# power_supply.net
KiCad netlist of a schematic drawn in Altium Designer
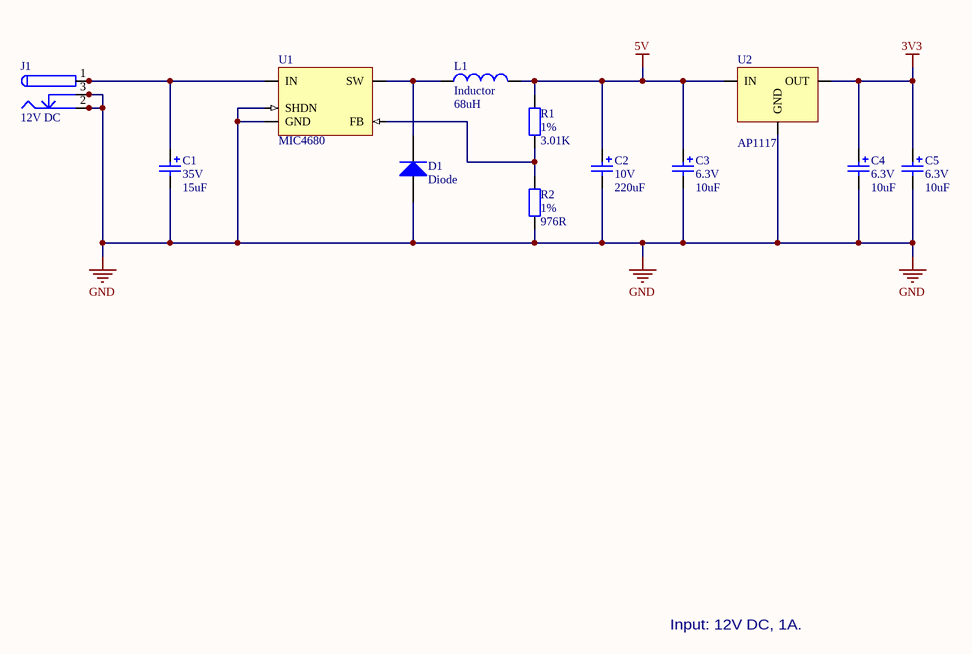
[diagram p0: power_supply.SchDoc]

(export (version "E")
  (design (tool "Eeschema 10.0.6"))
  (components
    (comp (ref "C1")
      (value "35V")
      (footprint "EIA-7343")
      (description "Polarized Capacitor (Axial)")
      (fields (field (name "ALTIUM_VALUE") "15uF") (field (name "PUBLISHER") "Altium Limited"))
      (libsource (lib "Miscellaneous Devices") (part "Cap Pol2"))
    )
    (comp (ref "C2")
      (value "10V")
      (footprint "EIA-7343")
      (description "Polarized Capacitor (Axial)")
      (fields (field (name "ALTIUM_VALUE") "220uF") (field (name "PUBLISHER") "Altium Limited"))
      (libsource (lib "Miscellaneous Devices") (part "Cap Pol2"))
    )
    (comp (ref "C3")
      (value "6.3V")
      (footprint "EIA-3216")
      (description "Polarized Capacitor (Axial)")
      (fields (field (name "ALTIUM_VALUE") "10uF") (field (name "PUBLISHER") "Altium Limited"))
      (libsource (lib "Miscellaneous Devices") (part "Cap Pol2"))
    )
    (comp (ref "C4")
      (value "6.3V")
      (footprint "EIA-3216")
      (description "Polarized Capacitor (Axial)")
      (fields (field (name "ALTIUM_VALUE") "10uF") (field (name "PUBLISHER") "Altium Limited"))
      (libsource (lib "Miscellaneous Devices") (part "Cap Pol2"))
    )
    (comp (ref "C5")
      (value "6.3V")
      (footprint "EIA-3216")
      (description "Polarized Capacitor (Axial)")
      (fields (field (name "ALTIUM_VALUE") "10uF") (field (name "PUBLISHER") "Altium Limited"))
      (libsource (lib "Miscellaneous Devices") (part "Cap Pol2"))
    )
    (comp (ref "D1")
      (value "Diode")
      (footprint "Diode (SMA)")
      (description "Default Diode")
      (fields (field (name "PUBLISHER") "Altium Limited"))
      (libsource (lib "Miscellaneous Devices") (part "Diode"))
    )
    (comp (ref "J1")
      (value "12V DC")
      (footprint "DC Jack")
      (description "Low Voltage Power Supply Connector")
      (fields (field (name "PUBLISHER") "Altium Limited"))
      (libsource (lib "Miscellaneous Connectors") (part "PWR2.5"))
    )
    (comp (ref "L1")
      (value "Inductor")
      (footprint "Inductor EPCOS")
      (fields (field (name "ALTIUM_VALUE") "68uH") (field (name "PUBLISHER") "Altium Limited"))
      (libsource (lib "Miscellaneous Devices") (part "Inductor"))
    )
    (comp (ref "R1")
      (value "1%")
      (footprint "0603")
      (description "Resistor")
      (fields (field (name "ALTIUM_VALUE") "3.01K") (field (name "PUBLISHER") "Altium Limited"))
      (libsource (lib "Miscellaneous Devices") (part "Res2"))
    )
    (comp (ref "R2")
      (value "1%")
      (footprint "0603")
      (description "Resistor")
      (fields (field (name "ALTIUM_VALUE") "976R") (field (name "PUBLISHER") "Altium Limited"))
      (libsource (lib "Miscellaneous Devices") (part "Res2"))
    )
    (comp (ref "U1")
      (value "MIC4680")
      (footprint "SO-8")
      (description "1A 200kHz Buck Regulator")
      (libsource (lib "AJ") (part "MIC4680"))
    )
    (comp (ref "U2")
      (value "AP1117")
      (footprint "TO252 HS")
      (description "Low Dropout Regulator")
      (libsource (lib "AJ") (part "AP1117"))
    )
  )
  (nets
    (net (code "1") (name "3V3") (class "Default")
      (node (ref "C4") (pin "1") (pinfunction "1_1") (pintype "passive"))
      (node (ref "C5") (pin "1") (pinfunction "1_1") (pintype "passive"))
      (node (ref "U2") (pin "2") (pinfunction "OUT_2") (pintype "passive"))
    )
    (net (code "2") (name "5V") (class "Default")
      (node (ref "C2") (pin "1") (pinfunction "1_1") (pintype "passive"))
      (node (ref "C3") (pin "1") (pinfunction "1_1") (pintype "passive"))
      (node (ref "L1") (pin "2") (pinfunction "2_2") (pintype "passive"))
      (node (ref "R1") (pin "2") (pinfunction "2_2") (pintype "passive"))
      (node (ref "U2") (pin "3") (pinfunction "IN_3") (pintype "passive"))
    )
    (net (code "3") (name "GND") (class "Default")
      (node (ref "C1") (pin "2") (pinfunction "2_2") (pintype "passive"))
      (node (ref "C2") (pin "2") (pinfunction "2_2") (pintype "passive"))
      (node (ref "C3") (pin "2") (pinfunction "2_2") (pintype "passive"))
      (node (ref "C4") (pin "2") (pinfunction "2_2") (pintype "passive"))
      (node (ref "C5") (pin "2") (pinfunction "2_2") (pintype "passive"))
      (node (ref "D1") (pin "1") (pinfunction "A_1") (pintype "passive"))
      (node (ref "J1") (pin "2") (pinfunction "2_2") (pintype "power_in"))
      (node (ref "J1") (pin "2A") (pinfunction "2A_2A") (pintype "power_in"))
      (node (ref "J1") (pin "2B") (pinfunction "2B_2B") (pintype "power_in"))
      (node (ref "J1") (pin "3") (pinfunction "3_3") (pintype "power_in"))
      (node (ref "J1") (pin "3A") (pinfunction "3A_3A") (pintype "power_in"))
      (node (ref "J1") (pin "3B") (pinfunction "3B_3B") (pintype "power_in"))
      (node (ref "R2") (pin "1") (pinfunction "1_1") (pintype "passive"))
      (node (ref "U1") (pin "1") (pinfunction "SHDN_1") (pintype "input"))
      (node (ref "U1") (pin "5") (pinfunction "GND_5") (pintype "power_in"))
      (node (ref "U1") (pin "6") (pinfunction "GND_6") (pintype "power_in"))
      (node (ref "U1") (pin "7") (pinfunction "GND_7") (pintype "power_in"))
      (node (ref "U1") (pin "8") (pinfunction "GND_8") (pintype "power_in"))
      (node (ref "U2") (pin "1") (pinfunction "GND_1") (pintype "power_in"))
    )
    (net (code "4") (name "Net-(D1-K)") (class "Default")
      (node (ref "D1") (pin "2") (pinfunction "K_2") (pintype "passive"))
      (node (ref "L1") (pin "1") (pinfunction "1_1") (pintype "passive"))
      (node (ref "U1") (pin "3") (pinfunction "SW_3") (pintype "passive"))
    )
    (net (code "5") (name "Net-(U1-FB)") (class "Default")
      (node (ref "R1") (pin "1") (pinfunction "1_1") (pintype "passive"))
      (node (ref "R2") (pin "2") (pinfunction "2_2") (pintype "passive"))
      (node (ref "U1") (pin "4") (pinfunction "FB_4") (pintype "input"))
    )
    (net (code "6") (name "Net-(U1-IN)") (class "Default")
      (node (ref "C1") (pin "1") (pinfunction "1_1") (pintype "passive"))
      (node (ref "J1") (pin "1") (pinfunction "1_1") (pintype "power_in"))
      (node (ref "J1") (pin "1A") (pinfunction "1A_1A") (pintype "power_in"))
      (node (ref "J1") (pin "1B") (pinfunction "1B_1B") (pintype "power_in"))
      (node (ref "U1") (pin "2") (pinfunction "IN_2") (pintype "passive"))
    )
  )
)
